# LED_Haptics_Module.net
KiCad netlist of a schematic drawn in EasyEDA Pro
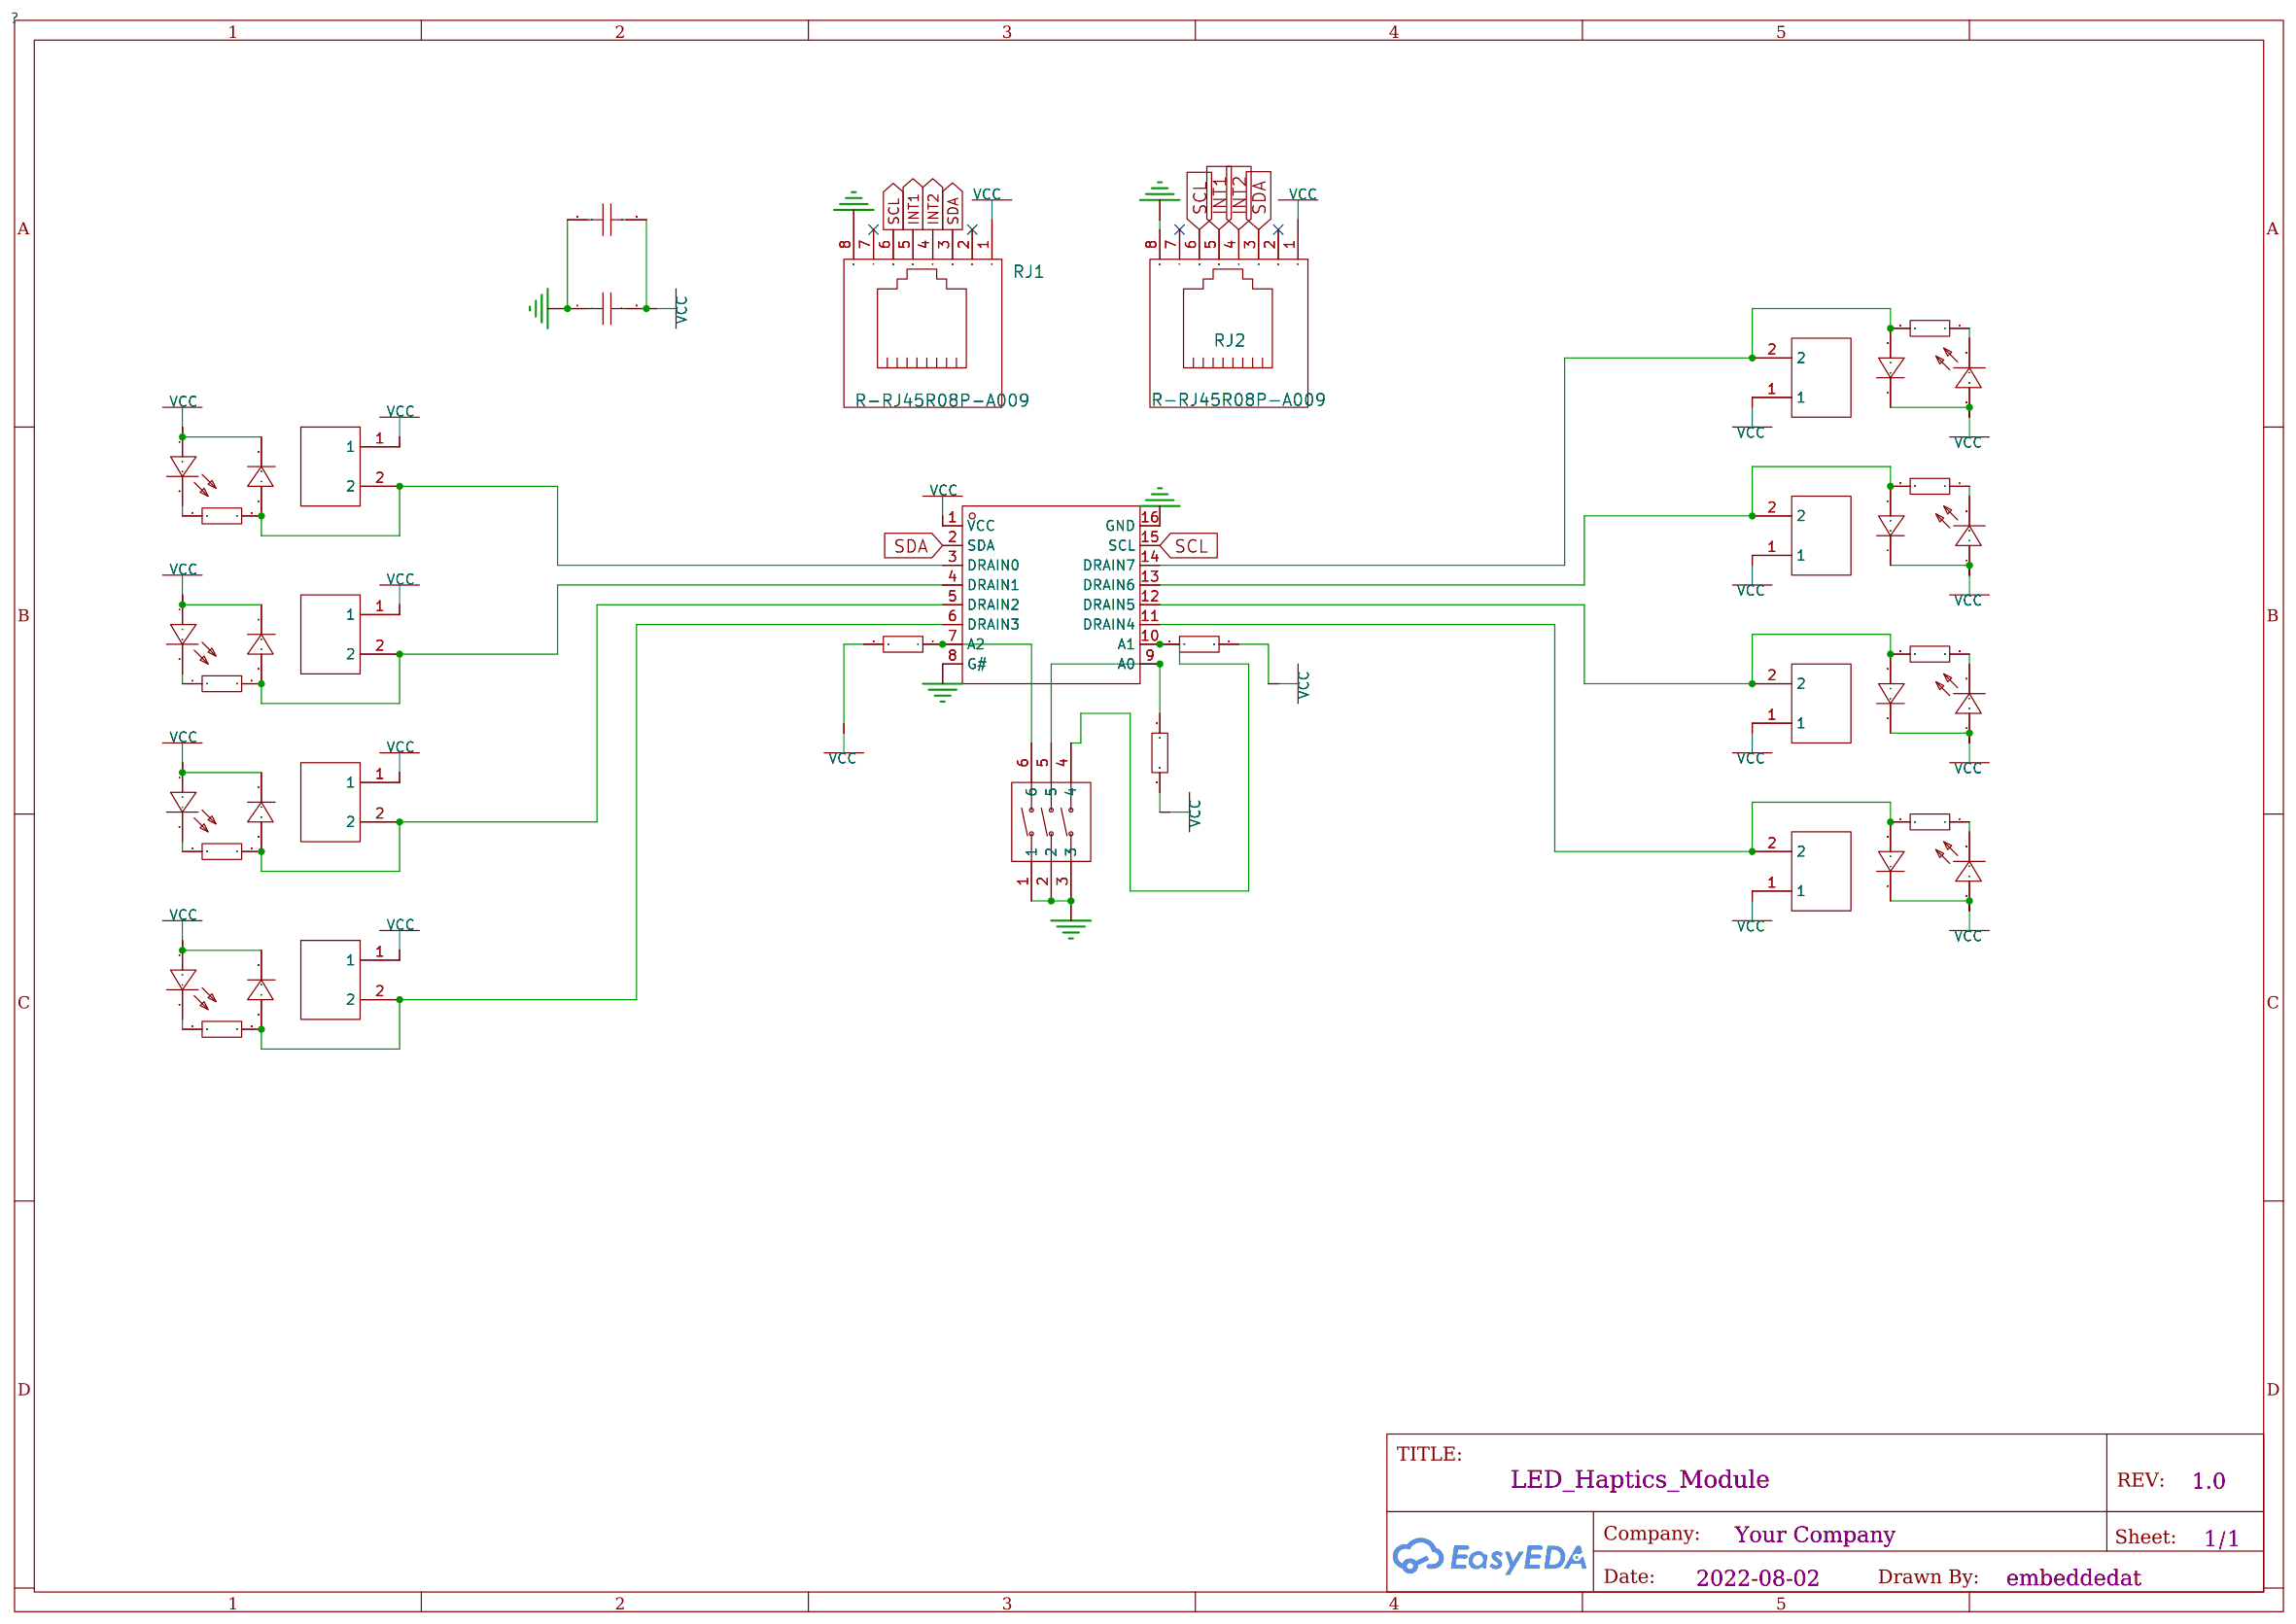
[diagram p0: schematic sheet]

(export (version "E")
  (design (tool "Eeschema 10.0.6"))
  (components
    (comp (ref "C3")
      (value "47uF")
      (footprint "easyedapro:C1206")
      (description "容值:47uF;精度:±20%;额定电压:10V;温度系数:X5R;")
      (fields
        (field (name "Manufacturer Part") "CL31A476MPHNNNE")
        (field (name "Manufacturer") "SAMSUNG(三星)")
      )
      (libsource (lib "easyedapro") (part "CL31A476MPHNNNE"))
    )
    (comp (ref "C4")
      (value "100nF")
      (footprint "easyedapro:C0402")
      (description "容值:100nF;精度:±10%;额定电压:50V;温度系数:X7R;")
      (fields
        (field (name "Manufacturer Part") "CL05B104KB54PNC")
        (field (name "Manufacturer") "SAMSUNG(三星)")
      )
      (libsource (lib "easyedapro") (part "CL05B104KB54PNC"))
    )
    (comp (ref "CN1")
      (value "B2B-PH-K-S(LF)(SN)")
      (footprint "easyedapro:CONN-TH_B2B-PH-K-S")
      (fields (field (name "Manufacturer") "JST"))
      (libsource (lib "easyedapro") (part "B2B-PH-K-S(LF)(SN)"))
    )
    (comp (ref "CN2")
      (value "B2B-PH-K-S(LF)(SN)")
      (footprint "easyedapro:CONN-TH_B2B-PH-K-S")
      (fields (field (name "Manufacturer") "JST"))
      (libsource (lib "easyedapro") (part "B2B-PH-K-S(LF)(SN)"))
    )
    (comp (ref "CN3")
      (value "B2B-PH-K-S(LF)(SN)")
      (footprint "easyedapro:CONN-TH_B2B-PH-K-S")
      (fields (field (name "Manufacturer") "JST"))
      (libsource (lib "easyedapro") (part "B2B-PH-K-S(LF)(SN)"))
    )
    (comp (ref "CN4")
      (value "B2B-PH-K-S(LF)(SN)")
      (footprint "easyedapro:CONN-TH_B2B-PH-K-S")
      (fields (field (name "Manufacturer") "JST"))
      (libsource (lib "easyedapro") (part "B2B-PH-K-S(LF)(SN)"))
    )
    (comp (ref "CN5")
      (value "B2B-PH-K-S(LF)(SN)")
      (footprint "easyedapro:CONN-TH_B2B-PH-K-S")
      (fields (field (name "Manufacturer") "JST"))
      (libsource (lib "easyedapro") (part "B2B-PH-K-S(LF)(SN)"))
    )
    (comp (ref "CN6")
      (value "B2B-PH-K-S(LF)(SN)")
      (footprint "easyedapro:CONN-TH_B2B-PH-K-S")
      (fields (field (name "Manufacturer") "JST"))
      (libsource (lib "easyedapro") (part "B2B-PH-K-S(LF)(SN)"))
    )
    (comp (ref "CN7")
      (value "B2B-PH-K-S(LF)(SN)")
      (footprint "easyedapro:CONN-TH_B2B-PH-K-S")
      (fields (field (name "Manufacturer") "JST"))
      (libsource (lib "easyedapro") (part "B2B-PH-K-S(LF)(SN)"))
    )
    (comp (ref "CN9")
      (value "B2B-PH-K-S(LF)(SN)")
      (footprint "easyedapro:CONN-TH_B2B-PH-K-S")
      (fields (field (name "Manufacturer") "JST"))
      (libsource (lib "easyedapro") (part "B2B-PH-K-S(LF)(SN)"))
    )
    (comp (ref "D1")
      (value "~")
      (footprint "easyedapro:DO-214AC_L4.3-W2.7-LS5.3-RD")
      (description "二极管配置:-;直流反向耐压(Vr):1kV;平均整流电流(Io):1A;正向压降(Vf):1.1V@1A;反向电流(Ir):5A@1kV;")
      (fields (field (name "Manufacturer Part") "M7") (field (name "Manufacturer") "MDD"))
      (libsource (lib "easyedapro") (part "M7_C95872"))
    )
    (comp (ref "D2")
      (value "~")
      (footprint "easyedapro:DO-214AC_L4.3-W2.7-LS5.3-RD")
      (description "二极管配置:-;直流反向耐压(Vr):1kV;平均整流电流(Io):1A;正向压降(Vf):1.1V@1A;反向电流(Ir):5A@1kV;")
      (fields (field (name "Manufacturer Part") "M7") (field (name "Manufacturer") "MDD"))
      (libsource (lib "easyedapro") (part "M7_C95872"))
    )
    (comp (ref "D3")
      (value "~")
      (footprint "easyedapro:DO-214AC_L4.3-W2.7-LS5.3-RD")
      (description "二极管配置:-;直流反向耐压(Vr):1kV;平均整流电流(Io):1A;正向压降(Vf):1.1V@1A;反向电流(Ir):5A@1kV;")
      (fields (field (name "Manufacturer Part") "M7") (field (name "Manufacturer") "MDD"))
      (libsource (lib "easyedapro") (part "M7_C95872"))
    )
    (comp (ref "D4")
      (value "~")
      (footprint "easyedapro:DO-214AC_L4.3-W2.7-LS5.3-RD")
      (description "二极管配置:-;直流反向耐压(Vr):1kV;平均整流电流(Io):1A;正向压降(Vf):1.1V@1A;反向电流(Ir):5A@1kV;")
      (fields (field (name "Manufacturer Part") "M7") (field (name "Manufacturer") "MDD"))
      (libsource (lib "easyedapro") (part "M7_C95872"))
    )
    (comp (ref "D5")
      (value "~")
      (footprint "easyedapro:DO-214AC_L4.3-W2.7-LS5.3-RD")
      (description "二极管配置:-;直流反向耐压(Vr):1kV;平均整流电流(Io):1A;正向压降(Vf):1.1V@1A;反向电流(Ir):5A@1kV;")
      (fields (field (name "Manufacturer Part") "M7") (field (name "Manufacturer") "MDD"))
      (libsource (lib "easyedapro") (part "M7_C95872"))
    )
    (comp (ref "D6")
      (value "~")
      (footprint "easyedapro:DO-214AC_L4.3-W2.7-LS5.3-RD")
      (description "二极管配置:-;直流反向耐压(Vr):1kV;平均整流电流(Io):1A;正向压降(Vf):1.1V@1A;反向电流(Ir):5A@1kV;")
      (fields (field (name "Manufacturer Part") "M7") (field (name "Manufacturer") "MDD"))
      (libsource (lib "easyedapro") (part "M7_C95872"))
    )
    (comp (ref "D7")
      (value "~")
      (footprint "easyedapro:DO-214AC_L4.3-W2.7-LS5.3-RD")
      (description "二极管配置:-;直流反向耐压(Vr):1kV;平均整流电流(Io):1A;正向压降(Vf):1.1V@1A;反向电流(Ir):5A@1kV;")
      (fields (field (name "Manufacturer Part") "M7") (field (name "Manufacturer") "MDD"))
      (libsource (lib "easyedapro") (part "M7_C95872"))
    )
    (comp (ref "D8")
      (value "~")
      (footprint "easyedapro:DO-214AC_L4.3-W2.7-LS5.3-RD")
      (description "二极管配置:-;直流反向耐压(Vr):1kV;平均整流电流(Io):1A;正向压降(Vf):1.1V@1A;反向电流(Ir):5A@1kV;")
      (fields (field (name "Manufacturer Part") "M7") (field (name "Manufacturer") "MDD"))
      (libsource (lib "easyedapro") (part "M7_C95872"))
    )
    (comp (ref "LED1")
      (value "~")
      (footprint "easyedapro:LED0603-R-RD")
      (fields (field (name "Manufacturer Part") "KT-0603R") (field (name "Manufacturer") "KENTO"))
      (libsource (lib "easyedapro") (part "KT-0603R"))
    )
    (comp (ref "LED2")
      (value "~")
      (footprint "easyedapro:LED0603-R-RD")
      (fields (field (name "Manufacturer Part") "KT-0603R") (field (name "Manufacturer") "KENTO"))
      (libsource (lib "easyedapro") (part "KT-0603R"))
    )
    (comp (ref "LED3")
      (value "~")
      (footprint "easyedapro:LED0603-R-RD")
      (fields (field (name "Manufacturer Part") "KT-0603R") (field (name "Manufacturer") "KENTO"))
      (libsource (lib "easyedapro") (part "KT-0603R"))
    )
    (comp (ref "LED4")
      (value "~")
      (footprint "easyedapro:LED0603-R-RD")
      (fields (field (name "Manufacturer Part") "KT-0603R") (field (name "Manufacturer") "KENTO"))
      (libsource (lib "easyedapro") (part "KT-0603R"))
    )
    (comp (ref "LED5")
      (value "~")
      (footprint "easyedapro:LED0603-R-RD")
      (fields (field (name "Manufacturer Part") "KT-0603R") (field (name "Manufacturer") "KENTO"))
      (libsource (lib "easyedapro") (part "KT-0603R"))
    )
    (comp (ref "LED6")
      (value "~")
      (footprint "easyedapro:LED0603-R-RD")
      (fields (field (name "Manufacturer Part") "KT-0603R") (field (name "Manufacturer") "KENTO"))
      (libsource (lib "easyedapro") (part "KT-0603R"))
    )
    (comp (ref "LED7")
      (value "~")
      (footprint "easyedapro:LED0603-R-RD")
      (fields (field (name "Manufacturer Part") "KT-0603R") (field (name "Manufacturer") "KENTO"))
      (libsource (lib "easyedapro") (part "KT-0603R"))
    )
    (comp (ref "LED8")
      (value "~")
      (footprint "easyedapro:LED0603-R-RD")
      (fields (field (name "Manufacturer Part") "KT-0603R") (field (name "Manufacturer") "KENTO"))
      (libsource (lib "easyedapro") (part "KT-0603R"))
    )
    (comp (ref "R1")
      (value "1kΩ")
      (footprint "easyedapro:R0603")
      (description "电阻类型:厚膜电阻;阻值:1kΩ;精度:±1%;功率:1/10W;温度系数:±100ppm/;最大工作电压:75V;工作温度范围:-55~+155;")
      (fields
        (field (name "Manufacturer Part") "0603WAF1001T5E")
        (field (name "Manufacturer") "UNI-ROYAL(厚声)")
      )
      (libsource (lib "easyedapro") (part "0603WAF1001T5E"))
    )
    (comp (ref "R2")
      (value "1kΩ")
      (footprint "easyedapro:R0603")
      (description "电阻类型:厚膜电阻;阻值:1kΩ;精度:±1%;功率:1/10W;温度系数:±100ppm/;最大工作电压:75V;工作温度范围:-55~+155;")
      (fields
        (field (name "Manufacturer Part") "0603WAF1001T5E")
        (field (name "Manufacturer") "UNI-ROYAL(厚声)")
      )
      (libsource (lib "easyedapro") (part "0603WAF1001T5E"))
    )
    (comp (ref "R3")
      (value "330Ω")
      (footprint "easyedapro:R0603")
      (description "电阻类型:厚膜电阻;阻值:330Ω;精度:±1%;功率:1/10W;温度系数:±100ppm/;最大工作电压:75V;工作温度范围:-55~+155;")
      (fields
        (field (name "Manufacturer Part") "0603WAF3300T5E")
        (field (name "Manufacturer") "UNI-ROYAL(厚声)")
      )
      (libsource (lib "easyedapro") (part "0603WAF3300T5E"))
    )
    (comp (ref "R4")
      (value "330Ω")
      (footprint "easyedapro:R0603")
      (description "电阻类型:厚膜电阻;阻值:330Ω;精度:±1%;功率:1/10W;温度系数:±100ppm/;最大工作电压:75V;工作温度范围:-55~+155;")
      (fields
        (field (name "Manufacturer Part") "0603WAF3300T5E")
        (field (name "Manufacturer") "UNI-ROYAL(厚声)")
      )
      (libsource (lib "easyedapro") (part "0603WAF3300T5E"))
    )
    (comp (ref "R5")
      (value "330Ω")
      (footprint "easyedapro:R0603")
      (description "电阻类型:厚膜电阻;阻值:330Ω;精度:±1%;功率:1/10W;温度系数:±100ppm/;最大工作电压:75V;工作温度范围:-55~+155;")
      (fields
        (field (name "Manufacturer Part") "0603WAF3300T5E")
        (field (name "Manufacturer") "UNI-ROYAL(厚声)")
      )
      (libsource (lib "easyedapro") (part "0603WAF3300T5E"))
    )
    (comp (ref "R6")
      (value "330Ω")
      (footprint "easyedapro:R0603")
      (description "电阻类型:厚膜电阻;阻值:330Ω;精度:±1%;功率:1/10W;温度系数:±100ppm/;最大工作电压:75V;工作温度范围:-55~+155;")
      (fields
        (field (name "Manufacturer Part") "0603WAF3300T5E")
        (field (name "Manufacturer") "UNI-ROYAL(厚声)")
      )
      (libsource (lib "easyedapro") (part "0603WAF3300T5E"))
    )
    (comp (ref "R7")
      (value "330Ω")
      (footprint "easyedapro:R0603")
      (description "电阻类型:厚膜电阻;阻值:330Ω;精度:±1%;功率:1/10W;温度系数:±100ppm/;最大工作电压:75V;工作温度范围:-55~+155;")
      (fields
        (field (name "Manufacturer Part") "0603WAF3300T5E")
        (field (name "Manufacturer") "UNI-ROYAL(厚声)")
      )
      (libsource (lib "easyedapro") (part "0603WAF3300T5E"))
    )
    (comp (ref "R8")
      (value "330Ω")
      (footprint "easyedapro:R0603")
      (description "电阻类型:厚膜电阻;阻值:330Ω;精度:±1%;功率:1/10W;温度系数:±100ppm/;最大工作电压:75V;工作温度范围:-55~+155;")
      (fields
        (field (name "Manufacturer Part") "0603WAF3300T5E")
        (field (name "Manufacturer") "UNI-ROYAL(厚声)")
      )
      (libsource (lib "easyedapro") (part "0603WAF3300T5E"))
    )
    (comp (ref "R9")
      (value "330Ω")
      (footprint "easyedapro:R0603")
      (description "电阻类型:厚膜电阻;阻值:330Ω;精度:±1%;功率:1/10W;温度系数:±100ppm/;最大工作电压:75V;工作温度范围:-55~+155;")
      (fields
        (field (name "Manufacturer Part") "0603WAF3300T5E")
        (field (name "Manufacturer") "UNI-ROYAL(厚声)")
      )
      (libsource (lib "easyedapro") (part "0603WAF3300T5E"))
    )
    (comp (ref "R10")
      (value "330Ω")
      (footprint "easyedapro:R0603")
      (description "电阻类型:厚膜电阻;阻值:330Ω;精度:±1%;功率:1/10W;温度系数:±100ppm/;最大工作电压:75V;工作温度范围:-55~+155;")
      (fields
        (field (name "Manufacturer Part") "0603WAF3300T5E")
        (field (name "Manufacturer") "UNI-ROYAL(厚声)")
      )
      (libsource (lib "easyedapro") (part "0603WAF3300T5E"))
    )
    (comp (ref "R20")
      (value "1kΩ")
      (footprint "easyedapro:R0603")
      (description "电阻类型:厚膜电阻;阻值:1kΩ;精度:±1%;功率:1/10W;温度系数:±100ppm/;最大工作电压:75V;工作温度范围:-55~+155;")
      (fields
        (field (name "Manufacturer Part") "0603WAF1001T5E")
        (field (name "Manufacturer") "UNI-ROYAL(厚声)")
      )
      (libsource (lib "easyedapro") (part "0603WAF1001T5E"))
    )
    (comp (ref "RJ1")
      (value "R-RJ45R08P-A009")
      (footprint "easyedapro:RJ45-TH_R-RJ45R08P-A009")
      (fields (field (name "Manufacturer") "Ckmtw(灿科盟)"))
      (libsource (lib "easyedapro") (part "R-RJ45R08P-A009"))
    )
    (comp (ref "RJ2")
      (value "R-RJ45R08P-A009")
      (footprint "easyedapro:RJ45-TH_R-RJ45R08P-A009")
      (fields (field (name "Manufacturer") "Ckmtw(灿科盟)"))
      (libsource (lib "easyedapro") (part "R-RJ45R08P-A009"))
    )
    (comp (ref "SW1")
      (value "EM-03KP")
      (footprint "easyedapro:SW-SMD_EM-03KP")
      (fields (field (name "Manufacturer") "HRO"))
      (libsource (lib "easyedapro") (part "EM-03KP"))
    )
    (comp (ref "U1")
      (value "TPIC2810DRG4")
      (footprint "easyedapro:SOIC-16_L9.9-W3.9-P1.27-LS6.0-BL")
      (fields (field (name "Manufacturer") "TI(德州仪器)"))
      (libsource (lib "easyedapro") (part "TPIC2810DRG4"))
    )
  )
  (nets
    (net (code "1") (name "GND") (class "Default")
      (node (ref "C3") (pin "1") (pinfunction "1_1") (pintype "input"))
      (node (ref "C4") (pin "1") (pinfunction "1_1") (pintype "input"))
      (node (ref "RJ1") (pin "8") (pinfunction "8_8") (pintype "input"))
      (node (ref "RJ2") (pin "8") (pinfunction "8_8") (pintype "input"))
      (node (ref "SW1") (pin "1") (pinfunction "1_1") (pintype "input"))
      (node (ref "SW1") (pin "2") (pinfunction "2_2") (pintype "input"))
      (node (ref "SW1") (pin "3") (pinfunction "3_3") (pintype "input"))
      (node (ref "U1") (pin "16") (pinfunction "GND_16") (pintype "input"))
      (node (ref "U1") (pin "8") (pinfunction "G#_8") (pintype "input"))
    )
    (net (code "2") (name "INT1") (class "Default")
      (node (ref "RJ1") (pin "5") (pinfunction "5_5") (pintype "input"))
      (node (ref "RJ2") (pin "5") (pinfunction "5_5") (pintype "input"))
    )
    (net (code "3") (name "INT2") (class "Default")
      (node (ref "RJ1") (pin "4") (pinfunction "4_4") (pintype "input"))
      (node (ref "RJ2") (pin "4") (pinfunction "4_4") (pintype "input"))
    )
    (net (code "4") (name "Net-(D1-A)") (class "Default")
      (node (ref "CN9") (pin "2") (pinfunction "2_2") (pintype "input"))
      (node (ref "D1") (pin "2") (pinfunction "A_2") (pintype "input"))
      (node (ref "R3") (pin "2") (pinfunction "2_2") (pintype "input"))
      (node (ref "U1") (pin "6") (pinfunction "DRAIN3_6") (pintype "input"))
    )
    (net (code "5") (name "Net-(D2-A)") (class "Default")
      (node (ref "CN1") (pin "2") (pinfunction "2_2") (pintype "input"))
      (node (ref "D2") (pin "2") (pinfunction "A_2") (pintype "input"))
      (node (ref "R4") (pin "2") (pinfunction "2_2") (pintype "input"))
      (node (ref "U1") (pin "5") (pinfunction "DRAIN2_5") (pintype "input"))
    )
    (net (code "6") (name "Net-(D3-A)") (class "Default")
      (node (ref "CN2") (pin "2") (pinfunction "2_2") (pintype "input"))
      (node (ref "D3") (pin "2") (pinfunction "A_2") (pintype "input"))
      (node (ref "R5") (pin "2") (pinfunction "2_2") (pintype "input"))
      (node (ref "U1") (pin "4") (pinfunction "DRAIN1_4") (pintype "input"))
    )
    (net (code "7") (name "Net-(D4-A)") (class "Default")
      (node (ref "CN3") (pin "2") (pinfunction "2_2") (pintype "input"))
      (node (ref "D4") (pin "2") (pinfunction "A_2") (pintype "input"))
      (node (ref "R6") (pin "2") (pinfunction "2_2") (pintype "input"))
      (node (ref "U1") (pin "3") (pinfunction "DRAIN0_3") (pintype "input"))
    )
    (net (code "8") (name "Net-(D5-A)") (class "Default")
      (node (ref "CN4") (pin "2") (pinfunction "2_2") (pintype "input"))
      (node (ref "D5") (pin "2") (pinfunction "A_2") (pintype "input"))
      (node (ref "R7") (pin "2") (pinfunction "2_2") (pintype "input"))
      (node (ref "U1") (pin "14") (pinfunction "DRAIN7_14") (pintype "input"))
    )
    (net (code "9") (name "Net-(D6-A)") (class "Default")
      (node (ref "CN5") (pin "2") (pinfunction "2_2") (pintype "input"))
      (node (ref "D6") (pin "2") (pinfunction "A_2") (pintype "input"))
      (node (ref "R8") (pin "2") (pinfunction "2_2") (pintype "input"))
      (node (ref "U1") (pin "13") (pinfunction "DRAIN6_13") (pintype "input"))
    )
    (net (code "10") (name "Net-(D7-A)") (class "Default")
      (node (ref "CN6") (pin "2") (pinfunction "2_2") (pintype "input"))
      (node (ref "D7") (pin "2") (pinfunction "A_2") (pintype "input"))
      (node (ref "R9") (pin "2") (pinfunction "2_2") (pintype "input"))
      (node (ref "U1") (pin "12") (pinfunction "DRAIN5_12") (pintype "input"))
    )
    (net (code "11") (name "Net-(D8-A)") (class "Default")
      (node (ref "CN7") (pin "2") (pinfunction "2_2") (pintype "input"))
      (node (ref "D8") (pin "2") (pinfunction "A_2") (pintype "input"))
      (node (ref "R10") (pin "2") (pinfunction "2_2") (pintype "input"))
      (node (ref "U1") (pin "11") (pinfunction "DRAIN4_11") (pintype "input"))
    )
    (net (code "12") (name "Net-(LED1-K)") (class "Default")
      (node (ref "LED1") (pin "2") (pinfunction "K_2") (pintype "input"))
      (node (ref "R3") (pin "1") (pinfunction "1_1") (pintype "input"))
    )
    (net (code "13") (name "Net-(LED2-K)") (class "Default")
      (node (ref "LED2") (pin "2") (pinfunction "K_2") (pintype "input"))
      (node (ref "R4") (pin "1") (pinfunction "1_1") (pintype "input"))
    )
    (net (code "14") (name "Net-(LED3-K)") (class "Default")
      (node (ref "LED3") (pin "2") (pinfunction "K_2") (pintype "input"))
      (node (ref "R5") (pin "1") (pinfunction "1_1") (pintype "input"))
    )
    (net (code "15") (name "Net-(LED4-K)") (class "Default")
      (node (ref "LED4") (pin "2") (pinfunction "K_2") (pintype "input"))
      (node (ref "R6") (pin "1") (pinfunction "1_1") (pintype "input"))
    )
    (net (code "16") (name "Net-(LED5-K)") (class "Default")
      (node (ref "LED5") (pin "2") (pinfunction "K_2") (pintype "input"))
      (node (ref "R7") (pin "1") (pinfunction "1_1") (pintype "input"))
    )
    (net (code "17") (name "Net-(LED6-K)") (class "Default")
      (node (ref "LED6") (pin "2") (pinfunction "K_2") (pintype "input"))
      (node (ref "R8") (pin "1") (pinfunction "1_1") (pintype "input"))
    )
    (net (code "18") (name "Net-(LED7-K)") (class "Default")
      (node (ref "LED7") (pin "2") (pinfunction "K_2") (pintype "input"))
      (node (ref "R9") (pin "1") (pinfunction "1_1") (pintype "input"))
    )
    (net (code "19") (name "Net-(LED8-K)") (class "Default")
      (node (ref "LED8") (pin "2") (pinfunction "K_2") (pintype "input"))
      (node (ref "R10") (pin "1") (pinfunction "1_1") (pintype "input"))
    )
    (net (code "20") (name "Net-(U1-A0)") (class "Default")
      (node (ref "R1") (pin "1") (pinfunction "1_1") (pintype "input"))
      (node (ref "SW1") (pin "5") (pinfunction "5_5") (pintype "input"))
      (node (ref "U1") (pin "9") (pinfunction "A0_9") (pintype "input"))
    )
    (net (code "21") (name "Net-(U1-A1)") (class "Default")
      (node (ref "R20") (pin "2") (pinfunction "2_2") (pintype "input"))
      (node (ref "SW1") (pin "4") (pinfunction "4_4") (pintype "input"))
      (node (ref "U1") (pin "10") (pinfunction "A1_10") (pintype "input"))
    )
    (net (code "22") (name "Net-(U1-A2)") (class "Default")
      (node (ref "R2") (pin "1") (pinfunction "1_1") (pintype "input"))
      (node (ref "SW1") (pin "6") (pinfunction "6_6") (pintype "input"))
      (node (ref "U1") (pin "7") (pinfunction "A2_7") (pintype "input"))
    )
    (net (code "23") (name "SCL") (class "Default")
      (node (ref "RJ1") (pin "6") (pinfunction "6_6") (pintype "input"))
      (node (ref "RJ2") (pin "6") (pinfunction "6_6") (pintype "input"))
      (node (ref "U1") (pin "15") (pinfunction "SCL_15") (pintype "input"))
    )
    (net (code "24") (name "SDA") (class "Default")
      (node (ref "RJ1") (pin "3") (pinfunction "3_3") (pintype "input"))
      (node (ref "RJ2") (pin "3") (pinfunction "3_3") (pintype "input"))
      (node (ref "U1") (pin "2") (pinfunction "SDA_2") (pintype "input"))
    )
    (net (code "25") (name "VCC") (class "Default")
      (node (ref "C3") (pin "2") (pinfunction "2_2") (pintype "input"))
      (node (ref "C4") (pin "2") (pinfunction "2_2") (pintype "input"))
      (node (ref "CN1") (pin "1") (pinfunction "1_1") (pintype "input"))
      (node (ref "CN2") (pin "1") (pinfunction "1_1") (pintype "input"))
      (node (ref "CN3") (pin "1") (pinfunction "1_1") (pintype "input"))
      (node (ref "CN4") (pin "1") (pinfunction "1_1") (pintype "input"))
      (node (ref "CN5") (pin "1") (pinfunction "1_1") (pintype "input"))
      (node (ref "CN6") (pin "1") (pinfunction "1_1") (pintype "input"))
      (node (ref "CN7") (pin "1") (pinfunction "1_1") (pintype "input"))
      (node (ref "CN9") (pin "1") (pinfunction "1_1") (pintype "input"))
      (node (ref "D1") (pin "1") (pinfunction "K_1") (pintype "input"))
      (node (ref "D2") (pin "1") (pinfunction "K_1") (pintype "input"))
      (node (ref "D3") (pin "1") (pinfunction "K_1") (pintype "input"))
      (node (ref "D4") (pin "1") (pinfunction "K_1") (pintype "input"))
      (node (ref "D5") (pin "1") (pinfunction "K_1") (pintype "input"))
      (node (ref "D6") (pin "1") (pinfunction "K_1") (pintype "input"))
      (node (ref "D7") (pin "1") (pinfunction "K_1") (pintype "input"))
      (node (ref "D8") (pin "1") (pinfunction "K_1") (pintype "input"))
      (node (ref "LED1") (pin "1") (pinfunction "A_1") (pintype "input"))
      (node (ref "LED2") (pin "1") (pinfunction "A_1") (pintype "input"))
      (node (ref "LED3") (pin "1") (pinfunction "A_1") (pintype "input"))
      (node (ref "LED4") (pin "1") (pinfunction "A_1") (pintype "input"))
      (node (ref "LED5") (pin "1") (pinfunction "A_1") (pintype "input"))
      (node (ref "LED6") (pin "1") (pinfunction "A_1") (pintype "input"))
      (node (ref "LED7") (pin "1") (pinfunction "A_1") (pintype "input"))
      (node (ref "LED8") (pin "1") (pinfunction "A_1") (pintype "input"))
      (node (ref "R1") (pin "2") (pinfunction "2_2") (pintype "input"))
      (node (ref "R2") (pin "2") (pinfunction "2_2") (pintype "input"))
      (node (ref "R20") (pin "1") (pinfunction "1_1") (pintype "input"))
      (node (ref "RJ1") (pin "1") (pinfunction "1_1") (pintype "input"))
      (node (ref "RJ2") (pin "1") (pinfunction "1_1") (pintype "input"))
      (node (ref "U1") (pin "1") (pinfunction "VCC_1") (pintype "input"))
    )
    (net (code "26") (name "unconnected-(RJ1-Pad2)") (class "Default")
      (node (ref "RJ1") (pin "2") (pinfunction "2_2") (pintype "input+no_connect"))
    )
    (net (code "27") (name "unconnected-(RJ1-Pad7)") (class "Default")
      (node (ref "RJ1") (pin "7") (pinfunction "7_7") (pintype "input+no_connect"))
    )
    (net (code "28") (name "unconnected-(RJ2-Pad2)") (class "Default")
      (node (ref "RJ2") (pin "2") (pinfunction "2_2") (pintype "input+no_connect"))
    )
    (net (code "29") (name "unconnected-(RJ2-Pad7)") (class "Default")
      (node (ref "RJ2") (pin "7") (pinfunction "7_7") (pintype "input+no_connect"))
    )
  )
)
